# STM32L151.net
KiCad netlist of a schematic drawn in Altium Designer
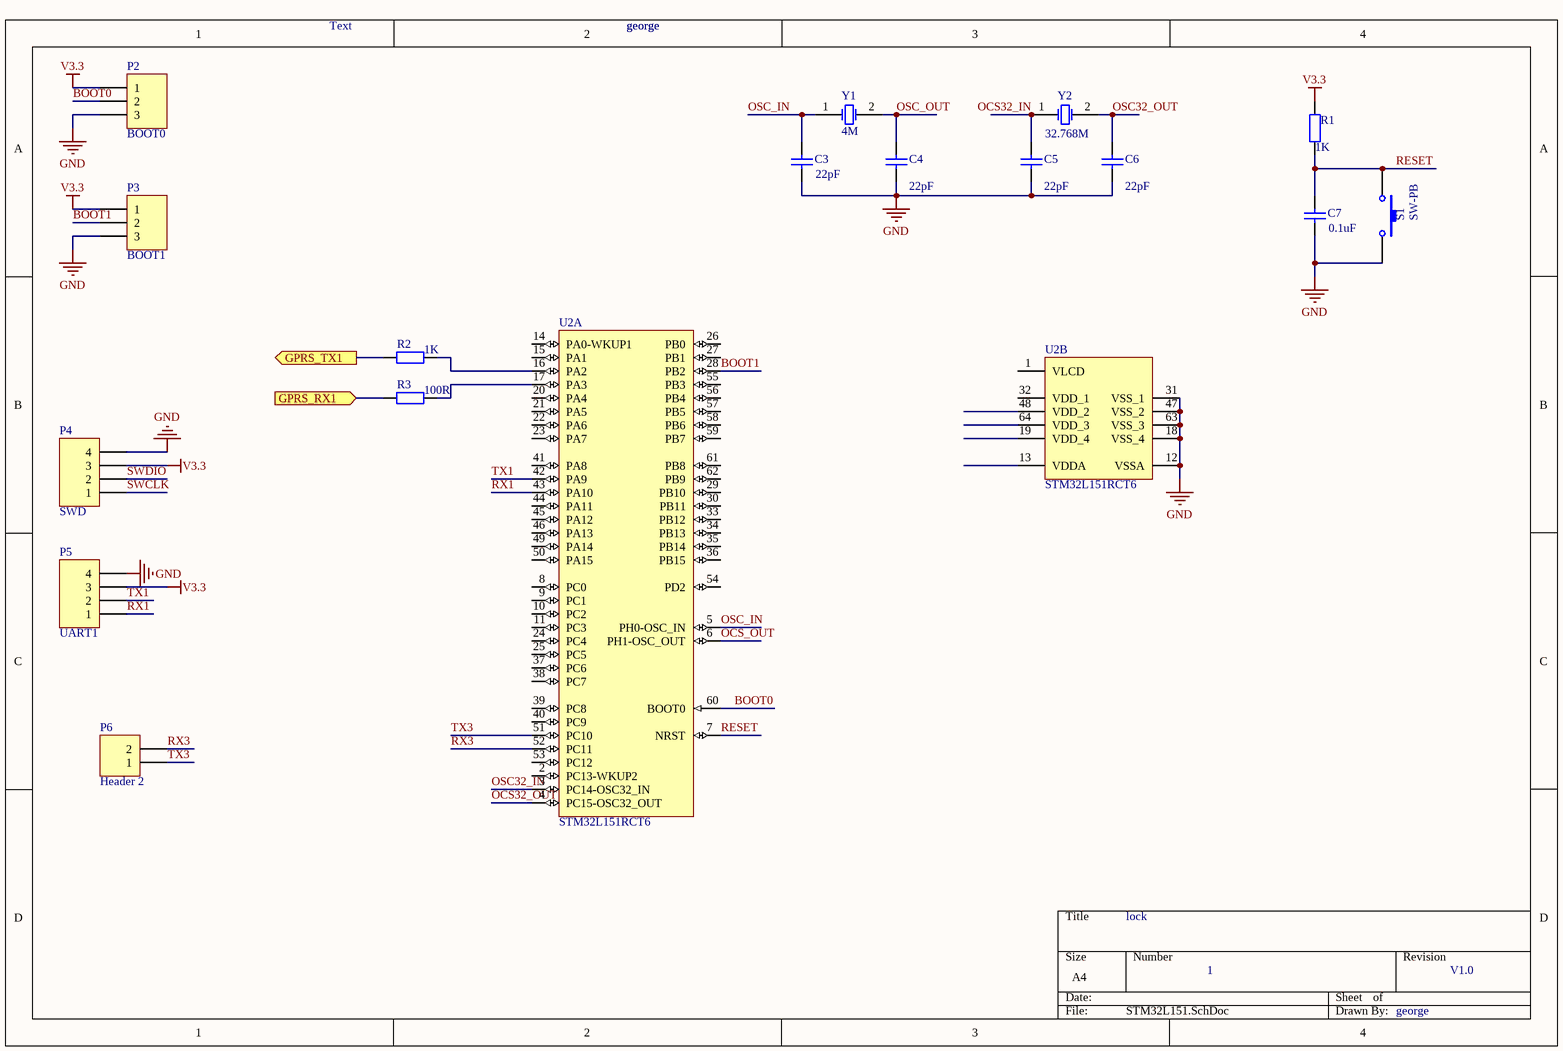
[diagram p0: STM32L151.SchDoc]

(export (version "E")
  (design (tool "Eeschema 10.0.6"))
  (components
    (comp (ref "C3")
      (value "22pF")
      (footprint "RAD-0.3")
      (description "Capacitor")
      (fields (field (name "Comment") "Cap") (field (name "PUBLISHER") "Altium Limited"))
      (libsource (lib "Miscellaneous Devices") (part "Cap"))
    )
    (comp (ref "C4")
      (value "22pF")
      (footprint "RAD-0.3")
      (description "Capacitor")
      (fields (field (name "Comment") "Cap") (field (name "PUBLISHER") "Altium Limited"))
      (libsource (lib "Miscellaneous Devices") (part "Cap"))
    )
    (comp (ref "C5")
      (value "22pF")
      (footprint "RAD-0.3")
      (description "Capacitor")
      (fields (field (name "Comment") "Cap") (field (name "PUBLISHER") "Altium Limited"))
      (libsource (lib "Miscellaneous Devices") (part "Cap"))
    )
    (comp (ref "C6")
      (value "22pF")
      (footprint "RAD-0.3")
      (description "Capacitor")
      (fields (field (name "Comment") "Cap") (field (name "PUBLISHER") "Altium Limited"))
      (libsource (lib "Miscellaneous Devices") (part "Cap"))
    )
    (comp (ref "C7")
      (value "0.1uF")
      (footprint "RAD-0.3")
      (description "Capacitor")
      (fields (field (name "Comment") "Cap") (field (name "PUBLISHER") "Altium Limited"))
      (libsource (lib "Miscellaneous Devices") (part "Cap"))
    )
    (comp (ref "P2")
      (value "BOOT0")
      (footprint "HDR1X3")
      (description "Header, 3-Pin")
      (fields (field (name "PUBLISHER") "Altium Limited"))
      (libsource (lib "Miscellaneous Connectors") (part "Header 3"))
    )
    (comp (ref "P3")
      (value "BOOT1")
      (footprint "HDR1X3")
      (description "Header, 3-Pin")
      (fields (field (name "PUBLISHER") "Altium Limited"))
      (libsource (lib "Miscellaneous Connectors") (part "Header 3"))
    )
    (comp (ref "P4")
      (value "SWD")
      (footprint "HDR1X4")
      (description "Header, 4-Pin")
      (fields (field (name "PUBLISHER") "Altium Limited"))
      (libsource (lib "Miscellaneous Connectors") (part "Header 4"))
    )
    (comp (ref "P5")
      (value "UART1")
      (footprint "HDR1X4")
      (description "Header, 4-Pin")
      (fields (field (name "PUBLISHER") "Altium Limited"))
      (libsource (lib "Miscellaneous Connectors") (part "Header 4"))
    )
    (comp (ref "P6")
      (value "Header 2")
      (footprint "HDR1X2")
      (description "Header, 2-Pin")
      (fields (field (name "PUBLISHER") "Altium Limited"))
      (libsource (lib "Miscellaneous Connectors") (part "Header 2"))
    )
    (comp (ref "R1")
      (value "1K")
      (footprint "AXIAL-0.4")
      (description "Resistor")
      (fields (field (name "Comment") "Res2") (field (name "PUBLISHER") "Altium Limited"))
      (libsource (lib "") (part "Res2_1"))
    )
    (comp (ref "R2")
      (value "1K")
      (footprint "AXIAL-0.4")
      (description "Resistor")
      (fields (field (name "Comment") "Res2") (field (name "PUBLISHER") "Altium Limited"))
      (libsource (lib "Miscellaneous Devices") (part "Res2"))
    )
    (comp (ref "R3")
      (value "100R")
      (footprint "AXIAL-0.4")
      (description "Resistor")
      (fields (field (name "Comment") "Res2") (field (name "PUBLISHER") "Altium Limited"))
      (libsource (lib "Miscellaneous Devices") (part "Res2"))
    )
    (comp (ref "S1")
      (value "SW-PB")
      (footprint "SPST-2")
      (description "Switch")
      (fields (field (name "PUBLISHER") "Altium Limited"))
      (libsource (lib "Miscellaneous Devices") (part "SW-PB"))
    )
    (comp (ref "U2")
      (value "STM32L151RCT6")
      (footprint "STM-LQFP64_N")
      (fields (field (name "MANUFACTURER") "STMicroelectronics"))
      (libsource (lib "STMicroelectronics STM32 L1") (part "STM32L151RCT6"))
    )
    (comp (ref "Y1")
      (value "4M")
      (footprint "R38")
      (description "Crystal Oscillator")
      (fields (field (name "PUBLISHER") "Altium Limited"))
      (libsource (lib "Miscellaneous Devices") (part "XTAL"))
    )
    (comp (ref "Y2")
      (value "32.768M")
      (footprint "R38")
      (description "Crystal Oscillator")
      (fields (field (name "PUBLISHER") "Altium Limited"))
      (libsource (lib "Miscellaneous Devices") (part "XTAL"))
    )
  )
  (nets
    (net (code "1") (name "/BOOT0") (class "Default")
      (node (ref "P2") (pin "2") (pinfunction "2_2") (pintype "passive"))
      (node (ref "U2") (pin "60") (pinfunction "BOOT0_60") (pintype "input"))
    )
    (net (code "2") (name "/BOOT1") (class "Default")
      (node (ref "P3") (pin "2") (pinfunction "2_2") (pintype "passive"))
      (node (ref "U2") (pin "28") (pinfunction "PB2_28") (pintype "bidirectional"))
    )
    (net (code "3") (name "/GPRS_RX1") (class "Default")
      (node (ref "R3") (pin "1") (pinfunction "1_1") (pintype "passive"))
    )
    (net (code "4") (name "/GPRS_TX1") (class "Default")
      (node (ref "R2") (pin "1") (pinfunction "1_1") (pintype "passive"))
    )
    (net (code "6") (name "/OCS32_OUT") (class "Default")
      (node (ref "U2") (pin "4") (pinfunction "PC15-OSC32_OUT_4") (pintype "bidirectional"))
    )
    (net (code "7") (name "/OCS_OUT") (class "Default")
      (node (ref "U2") (pin "6") (pinfunction "PH1-OSC_OUT_6") (pintype "bidirectional"))
    )
    (net (code "8") (name "/OSC32_IN") (class "Default")
      (node (ref "U2") (pin "3") (pinfunction "PC14-OSC32_IN_3") (pintype "bidirectional"))
    )
    (net (code "9") (name "/OSC32_OUT") (class "Default")
      (node (ref "C6") (pin "2") (pinfunction "2_2") (pintype "passive"))
      (node (ref "Y2") (pin "2") (pinfunction "OSC2_2") (pintype "passive"))
    )
    (net (code "10") (name "/OSC_IN") (class "Default")
      (node (ref "C3") (pin "2") (pinfunction "2_2") (pintype "passive"))
      (node (ref "U2") (pin "5") (pinfunction "PH0-OSC_IN_5") (pintype "bidirectional"))
      (node (ref "Y1") (pin "1") (pinfunction "OSC1_1") (pintype "passive"))
    )
    (net (code "11") (name "/OSC_OUT") (class "Default")
      (node (ref "C4") (pin "2") (pinfunction "2_2") (pintype "passive"))
      (node (ref "Y1") (pin "2") (pinfunction "OSC2_2") (pintype "passive"))
    )
    (net (code "12") (name "/RESET") (class "Default")
      (node (ref "C7") (pin "1") (pinfunction "1_1") (pintype "passive"))
      (node (ref "R1") (pin "2") (pinfunction "2_2") (pintype "passive"))
      (node (ref "S1") (pin "1") (pinfunction "1_1") (pintype "passive"))
      (node (ref "U2") (pin "7") (pinfunction "NRST_7") (pintype "bidirectional"))
    )
    (net (code "13") (name "/RX1") (class "Default")
      (node (ref "P5") (pin "1") (pinfunction "1_1") (pintype "passive"))
      (node (ref "U2") (pin "43") (pinfunction "PA10_43") (pintype "bidirectional"))
    )
    (net (code "14") (name "/RX3") (class "Default")
      (node (ref "P6") (pin "2") (pinfunction "2_2") (pintype "passive"))
      (node (ref "U2") (pin "52") (pinfunction "PC11_52") (pintype "bidirectional"))
    )
    (net (code "15") (name "/SWCLK") (class "Default")
      (node (ref "P4") (pin "1") (pinfunction "1_1") (pintype "passive"))
    )
    (net (code "16") (name "/SWDIO") (class "Default")
      (node (ref "P4") (pin "2") (pinfunction "2_2") (pintype "passive"))
    )
    (net (code "17") (name "/TX1") (class "Default")
      (node (ref "P5") (pin "2") (pinfunction "2_2") (pintype "passive"))
      (node (ref "U2") (pin "42") (pinfunction "PA9_42") (pintype "bidirectional"))
    )
    (net (code "18") (name "/TX3") (class "Default")
      (node (ref "P6") (pin "1") (pinfunction "1_1") (pintype "passive"))
      (node (ref "U2") (pin "51") (pinfunction "PC10_51") (pintype "bidirectional"))
    )
    (net (code "19") (name "GND") (class "Default")
      (node (ref "C3") (pin "1") (pinfunction "1_1") (pintype "passive"))
      (node (ref "C4") (pin "1") (pinfunction "1_1") (pintype "passive"))
      (node (ref "C5") (pin "1") (pinfunction "1_1") (pintype "passive"))
      (node (ref "C6") (pin "1") (pinfunction "1_1") (pintype "passive"))
      (node (ref "C7") (pin "2") (pinfunction "2_2") (pintype "passive"))
      (node (ref "P2") (pin "3") (pinfunction "3_3") (pintype "passive"))
      (node (ref "P3") (pin "3") (pinfunction "3_3") (pintype "passive"))
      (node (ref "P4") (pin "4") (pinfunction "4_4") (pintype "passive"))
      (node (ref "P5") (pin "4") (pinfunction "4_4") (pintype "passive"))
      (node (ref "S1") (pin "2") (pinfunction "2_2") (pintype "passive"))
      (node (ref "U2") (pin "12") (pinfunction "VSSA_12") (pintype "power_in"))
      (node (ref "U2") (pin "18") (pinfunction "VSS_4_18") (pintype "power_in"))
      (node (ref "U2") (pin "31") (pinfunction "VSS_1_31") (pintype "power_in"))
      (node (ref "U2") (pin "47") (pinfunction "VSS_2_47") (pintype "power_in"))
      (node (ref "U2") (pin "63") (pinfunction "VSS_3_63") (pintype "power_in"))
    )
    (net (code "20") (name "Net-(U2A-PA2)") (class "Default")
      (node (ref "R2") (pin "2") (pinfunction "2_2") (pintype "passive"))
      (node (ref "U2") (pin "16") (pinfunction "PA2_16") (pintype "bidirectional"))
    )
    (net (code "21") (name "Net-(U2A-PA3)") (class "Default")
      (node (ref "R3") (pin "2") (pinfunction "2_2") (pintype "passive"))
      (node (ref "U2") (pin "17") (pinfunction "PA3_17") (pintype "bidirectional"))
    )
    (net (code "22") (name "Net-(Y2-OSC1)") (class "Default")
      (node (ref "C5") (pin "2") (pinfunction "2_2") (pintype "passive"))
      (node (ref "Y2") (pin "1") (pinfunction "OSC1_1") (pintype "passive"))
    )
    (net (code "23") (name "V3.3") (class "Default")
      (node (ref "P2") (pin "1") (pinfunction "1_1") (pintype "passive"))
      (node (ref "P3") (pin "1") (pinfunction "1_1") (pintype "passive"))
      (node (ref "P4") (pin "3") (pinfunction "3_3") (pintype "passive"))
      (node (ref "P5") (pin "3") (pinfunction "3_3") (pintype "passive"))
      (node (ref "R1") (pin "1") (pinfunction "1_1") (pintype "passive"))
    )
    (net (code "24") (name "unconnected-(U2A-PA0-WKUP1-Pad14)") (class "Default")
      (node (ref "U2") (pin "14") (pinfunction "PA0-WKUP1_14") (pintype "bidirectional"))
    )
    (net (code "25") (name "unconnected-(U2A-PA1-Pad15)") (class "Default")
      (node (ref "U2") (pin "15") (pinfunction "PA1_15") (pintype "bidirectional"))
    )
    (net (code "26") (name "unconnected-(U2A-PA4-Pad20)") (class "Default")
      (node (ref "U2") (pin "20") (pinfunction "PA4_20") (pintype "bidirectional"))
    )
    (net (code "27") (name "unconnected-(U2A-PA5-Pad21)") (class "Default")
      (node (ref "U2") (pin "21") (pinfunction "PA5_21") (pintype "bidirectional"))
    )
    (net (code "28") (name "unconnected-(U2A-PA6-Pad22)") (class "Default")
      (node (ref "U2") (pin "22") (pinfunction "PA6_22") (pintype "bidirectional"))
    )
    (net (code "29") (name "unconnected-(U2A-PA7-Pad23)") (class "Default")
      (node (ref "U2") (pin "23") (pinfunction "PA7_23") (pintype "bidirectional"))
    )
    (net (code "30") (name "unconnected-(U2A-PA8-Pad41)") (class "Default")
      (node (ref "U2") (pin "41") (pinfunction "PA8_41") (pintype "bidirectional"))
    )
    (net (code "31") (name "unconnected-(U2A-PA11-Pad44)") (class "Default")
      (node (ref "U2") (pin "44") (pinfunction "PA11_44") (pintype "bidirectional"))
    )
    (net (code "32") (name "unconnected-(U2A-PA12-Pad45)") (class "Default")
      (node (ref "U2") (pin "45") (pinfunction "PA12_45") (pintype "bidirectional"))
    )
    (net (code "33") (name "unconnected-(U2A-PA13-Pad46)") (class "Default")
      (node (ref "U2") (pin "46") (pinfunction "PA13_46") (pintype "bidirectional"))
    )
    (net (code "34") (name "unconnected-(U2A-PA14-Pad49)") (class "Default")
      (node (ref "U2") (pin "49") (pinfunction "PA14_49") (pintype "bidirectional"))
    )
    (net (code "35") (name "unconnected-(U2A-PA15-Pad50)") (class "Default")
      (node (ref "U2") (pin "50") (pinfunction "PA15_50") (pintype "bidirectional"))
    )
    (net (code "36") (name "unconnected-(U2A-PB0-Pad26)") (class "Default")
      (node (ref "U2") (pin "26") (pinfunction "PB0_26") (pintype "bidirectional"))
    )
    (net (code "37") (name "unconnected-(U2A-PB1-Pad27)") (class "Default")
      (node (ref "U2") (pin "27") (pinfunction "PB1_27") (pintype "bidirectional"))
    )
    (net (code "38") (name "unconnected-(U2A-PB3-Pad55)") (class "Default")
      (node (ref "U2") (pin "55") (pinfunction "PB3_55") (pintype "bidirectional"))
    )
    (net (code "39") (name "unconnected-(U2A-PB4-Pad56)") (class "Default")
      (node (ref "U2") (pin "56") (pinfunction "PB4_56") (pintype "bidirectional"))
    )
    (net (code "40") (name "unconnected-(U2A-PB5-Pad57)") (class "Default")
      (node (ref "U2") (pin "57") (pinfunction "PB5_57") (pintype "bidirectional"))
    )
    (net (code "41") (name "unconnected-(U2A-PB6-Pad58)") (class "Default")
      (node (ref "U2") (pin "58") (pinfunction "PB6_58") (pintype "bidirectional"))
    )
    (net (code "42") (name "unconnected-(U2A-PB7-Pad59)") (class "Default")
      (node (ref "U2") (pin "59") (pinfunction "PB7_59") (pintype "bidirectional"))
    )
    (net (code "43") (name "unconnected-(U2A-PB8-Pad61)") (class "Default")
      (node (ref "U2") (pin "61") (pinfunction "PB8_61") (pintype "bidirectional"))
    )
    (net (code "44") (name "unconnected-(U2A-PB9-Pad62)") (class "Default")
      (node (ref "U2") (pin "62") (pinfunction "PB9_62") (pintype "bidirectional"))
    )
    (net (code "45") (name "unconnected-(U2A-PB10-Pad29)") (class "Default")
      (node (ref "U2") (pin "29") (pinfunction "PB10_29") (pintype "bidirectional"))
    )
    (net (code "46") (name "unconnected-(U2A-PB11-Pad30)") (class "Default")
      (node (ref "U2") (pin "30") (pinfunction "PB11_30") (pintype "bidirectional"))
    )
    (net (code "47") (name "unconnected-(U2A-PB12-Pad33)") (class "Default")
      (node (ref "U2") (pin "33") (pinfunction "PB12_33") (pintype "bidirectional"))
    )
    (net (code "48") (name "unconnected-(U2A-PB13-Pad34)") (class "Default")
      (node (ref "U2") (pin "34") (pinfunction "PB13_34") (pintype "bidirectional"))
    )
    (net (code "49") (name "unconnected-(U2A-PB14-Pad35)") (class "Default")
      (node (ref "U2") (pin "35") (pinfunction "PB14_35") (pintype "bidirectional"))
    )
    (net (code "50") (name "unconnected-(U2A-PB15-Pad36)") (class "Default")
      (node (ref "U2") (pin "36") (pinfunction "PB15_36") (pintype "bidirectional"))
    )
    (net (code "51") (name "unconnected-(U2A-PC0-Pad8)") (class "Default")
      (node (ref "U2") (pin "8") (pinfunction "PC0_8") (pintype "bidirectional"))
    )
    (net (code "52") (name "unconnected-(U2A-PC1-Pad9)") (class "Default")
      (node (ref "U2") (pin "9") (pinfunction "PC1_9") (pintype "bidirectional"))
    )
    (net (code "53") (name "unconnected-(U2A-PC2-Pad10)") (class "Default")
      (node (ref "U2") (pin "10") (pinfunction "PC2_10") (pintype "bidirectional"))
    )
    (net (code "54") (name "unconnected-(U2A-PC3-Pad11)") (class "Default")
      (node (ref "U2") (pin "11") (pinfunction "PC3_11") (pintype "bidirectional"))
    )
    (net (code "55") (name "unconnected-(U2A-PC4-Pad24)") (class "Default")
      (node (ref "U2") (pin "24") (pinfunction "PC4_24") (pintype "bidirectional"))
    )
    (net (code "56") (name "unconnected-(U2A-PC5-Pad25)") (class "Default")
      (node (ref "U2") (pin "25") (pinfunction "PC5_25") (pintype "bidirectional"))
    )
    (net (code "57") (name "unconnected-(U2A-PC6-Pad37)") (class "Default")
      (node (ref "U2") (pin "37") (pinfunction "PC6_37") (pintype "bidirectional"))
    )
    (net (code "58") (name "unconnected-(U2A-PC7-Pad38)") (class "Default")
      (node (ref "U2") (pin "38") (pinfunction "PC7_38") (pintype "bidirectional"))
    )
    (net (code "59") (name "unconnected-(U2A-PC8-Pad39)") (class "Default")
      (node (ref "U2") (pin "39") (pinfunction "PC8_39") (pintype "bidirectional"))
    )
    (net (code "60") (name "unconnected-(U2A-PC9-Pad40)") (class "Default")
      (node (ref "U2") (pin "40") (pinfunction "PC9_40") (pintype "bidirectional"))
    )
    (net (code "61") (name "unconnected-(U2A-PC12-Pad53)") (class "Default")
      (node (ref "U2") (pin "53") (pinfunction "PC12_53") (pintype "bidirectional"))
    )
    (net (code "62") (name "unconnected-(U2A-PC13-WKUP2-Pad2)") (class "Default")
      (node (ref "U2") (pin "2") (pinfunction "PC13-WKUP2_2") (pintype "bidirectional"))
    )
    (net (code "63") (name "unconnected-(U2A-PD2-Pad54)") (class "Default")
      (node (ref "U2") (pin "54") (pinfunction "PD2_54") (pintype "bidirectional"))
    )
    (net (code "64") (name "unconnected-(U2B-VDDA-Pad13)") (class "Default")
      (node (ref "U2") (pin "13") (pinfunction "VDDA_13") (pintype "power_in"))
    )
    (net (code "65") (name "unconnected-(U2B-VDD_1-Pad32)") (class "Default")
      (node (ref "U2") (pin "32") (pinfunction "VDD_1_32") (pintype "power_in"))
    )
    (net (code "66") (name "unconnected-(U2B-VDD_2-Pad48)") (class "Default")
      (node (ref "U2") (pin "48") (pinfunction "VDD_2_48") (pintype "power_in"))
    )
    (net (code "67") (name "unconnected-(U2B-VDD_3-Pad64)") (class "Default")
      (node (ref "U2") (pin "64") (pinfunction "VDD_3_64") (pintype "power_in"))
    )
    (net (code "68") (name "unconnected-(U2B-VDD_4-Pad19)") (class "Default")
      (node (ref "U2") (pin "19") (pinfunction "VDD_4_19") (pintype "power_in"))
    )
    (net (code "69") (name "unconnected-(U2B-VLCD-Pad1)") (class "Default")
      (node (ref "U2") (pin "1") (pinfunction "VLCD_1") (pintype "power_in"))
    )
  )
)
